# BMP085_Breakout-v14.net
KiCad netlist of a schematic drawn in EAGLE
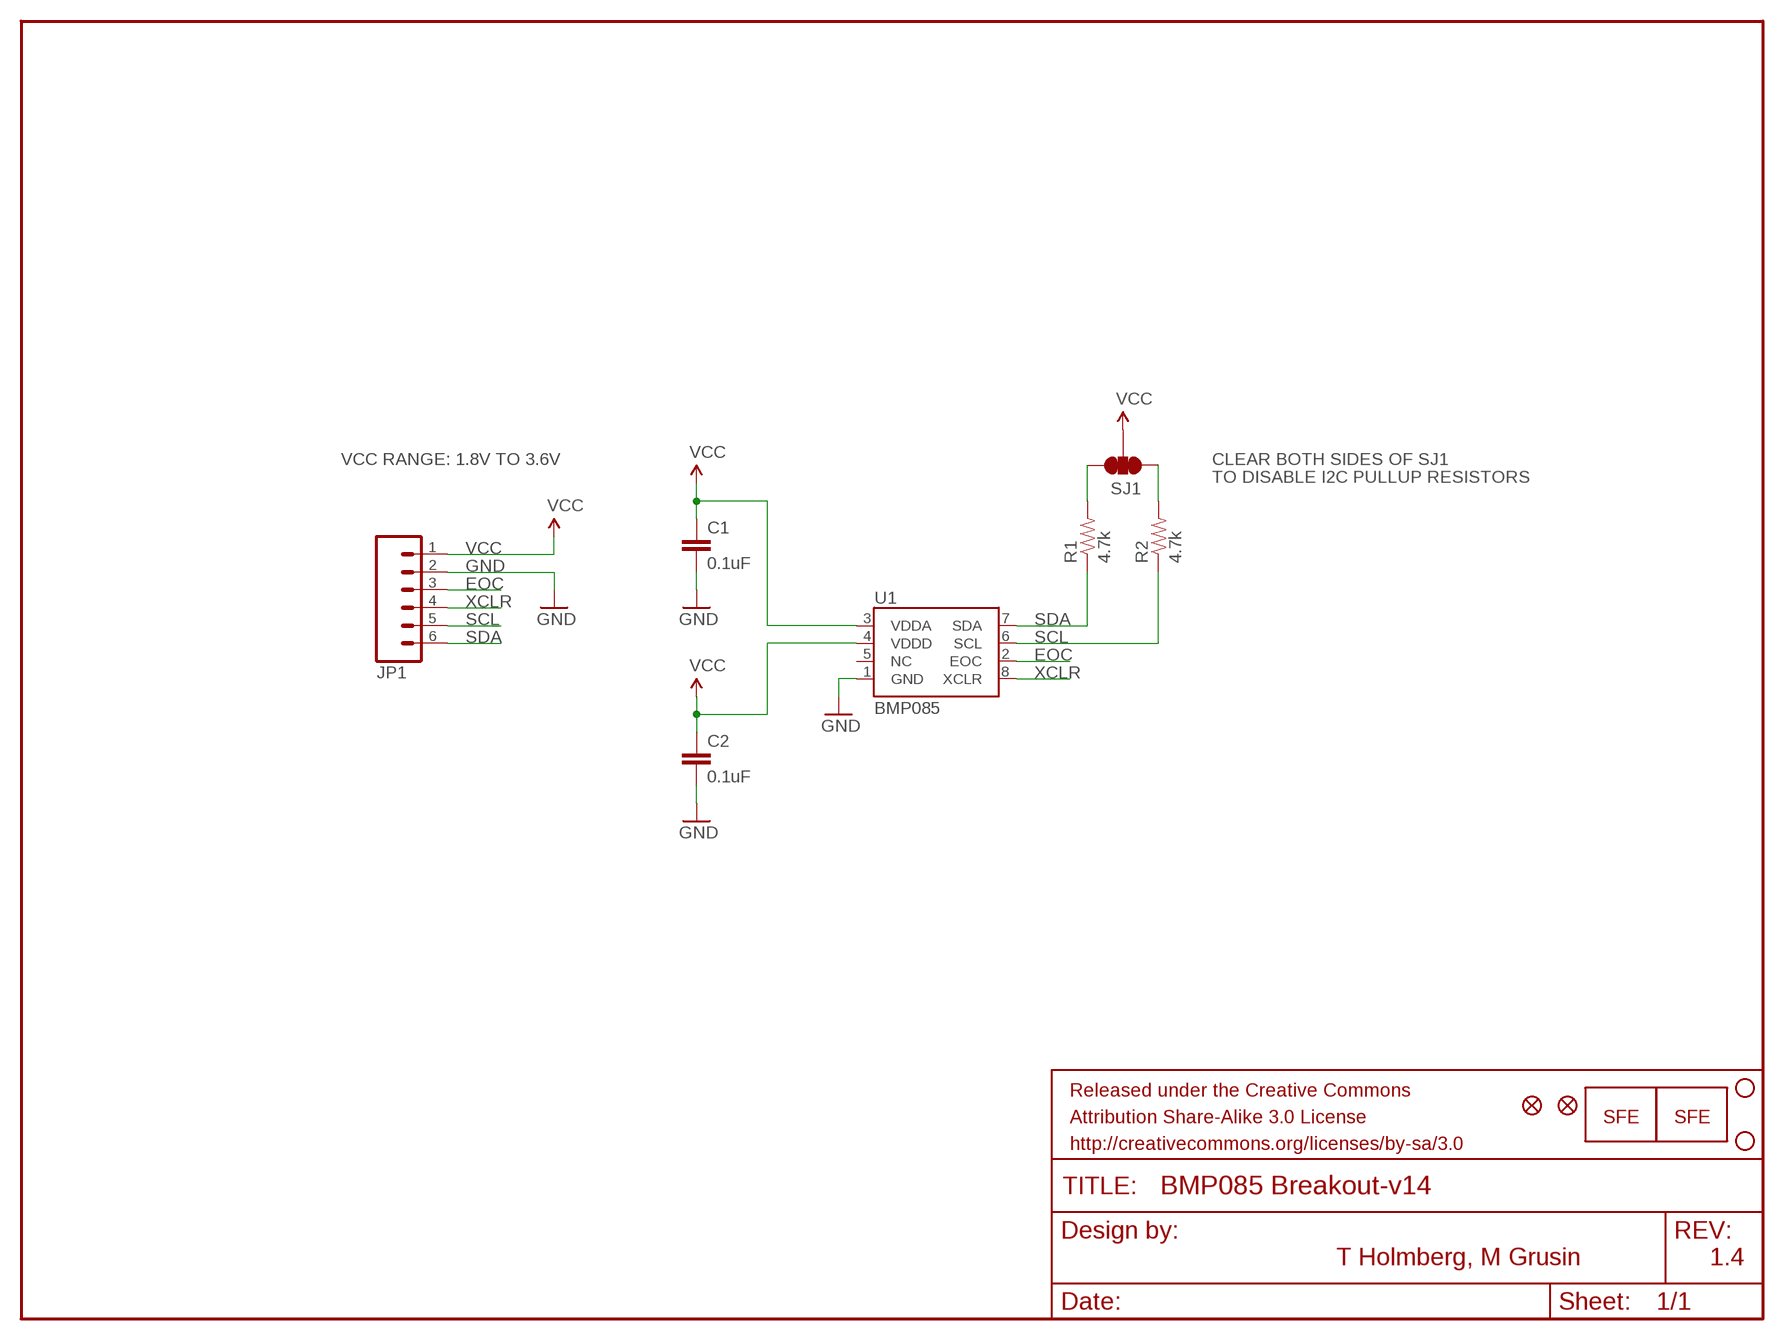
[diagram p0: schematic, sheet 1]

(export (version "E")
  (design (tool "Eeschema 10.0.6"))
  (components
    (comp (ref "C1")
      (value "0.1uF")
      (footprint "eagle-import:0402-CAP")
      (libsource (lib "eagle-import") (part "CAP0402-CAP"))
    )
    (comp (ref "C2")
      (value "0.1uF")
      (footprint "eagle-import:0402-CAP")
      (libsource (lib "eagle-import") (part "CAP0402-CAP"))
    )
    (comp (ref "JP1")
      (value "M06SIP")
      (footprint "eagle-import:1X06")
      (libsource (lib "eagle-import") (part "M06SIP"))
    )
    (comp (ref "JP2")
      (value "LOGO-SFENW2")
      (footprint "eagle-import:SFE-NEW-WEB")
      (libsource (lib "eagle-import") (part "SparkFun-Aesthetics_LOGO-SFENW2"))
    )
    (comp (ref "JP3")
      (value "FIDUCIALUFIDUCIAL")
      (footprint "eagle-import:MICRO-FIDUCIAL")
      (libsource (lib "eagle-import") (part "FIDUCIALUFIDUCIAL"))
    )
    (comp (ref "JP4")
      (value "FIDUCIALUFIDUCIAL")
      (footprint "eagle-import:MICRO-FIDUCIAL")
      (libsource (lib "eagle-import") (part "FIDUCIALUFIDUCIAL"))
    )
    (comp (ref "LOGO1")
      (value "LOGO-SFESK")
      (footprint "eagle-import:SFE-LOGO-FLAME")
      (libsource (lib "eagle-import") (part "LOGO-SFESK"))
    )
    (comp (ref "R1")
      (value "4.7k")
      (footprint "eagle-import:0402-RES")
      (libsource (lib "eagle-import") (part "RESISTOR0402-RES"))
    )
    (comp (ref "R2")
      (value "4.7k")
      (footprint "eagle-import:0402-RES")
      (libsource (lib "eagle-import") (part "RESISTOR0402-RES"))
    )
    (comp (ref "SJ1")
      (value "SOLDERJUMPER_2WAYPASTE1&2&3")
      (footprint "eagle-import:SJ_3_PASTE1&2&3")
      (libsource (lib "eagle-import") (part "SOLDERJUMPER_2WAYPASTE1&2&3"))
    )
    (comp (ref "STANDOFF1")
      (value "STAND-OFF")
      (footprint "eagle-import:STAND-OFF")
      (libsource (lib "eagle-import") (part "STAND-OFF"))
    )
    (comp (ref "STANDOFF2")
      (value "STAND-OFF")
      (footprint "eagle-import:STAND-OFF")
      (libsource (lib "eagle-import") (part "STAND-OFF"))
    )
    (comp (ref "U1")
      (value "BMP085")
      (footprint "eagle-import:BMP085")
      (libsource (lib "eagle-import") (part "BMP085"))
    )
  )
  (nets
    (net (code "1") (name "/EOC") (class "Default")
      (node (ref "JP1") (pin "3") (pinfunction "3_3") (pintype "passive"))
      (node (ref "U1") (pin "2") (pinfunction "EOC_2") (pintype "output"))
    )
    (net (code "2") (name "/SCL") (class "Default")
      (node (ref "JP1") (pin "5") (pinfunction "5_5") (pintype "passive"))
      (node (ref "R2") (pin "1") (pinfunction "1_1") (pintype "passive"))
      (node (ref "U1") (pin "6") (pinfunction "SCL_6") (pintype "input"))
    )
    (net (code "3") (name "/SDA") (class "Default")
      (node (ref "JP1") (pin "6") (pinfunction "6_6") (pintype "passive"))
      (node (ref "R1") (pin "1") (pinfunction "1_1") (pintype "passive"))
      (node (ref "U1") (pin "7") (pinfunction "SDA_7") (pintype "bidirectional"))
    )
    (net (code "4") (name "/XCLR") (class "Default")
      (node (ref "JP1") (pin "4") (pinfunction "4_4") (pintype "passive"))
      (node (ref "U1") (pin "8") (pinfunction "XCLR_8") (pintype "input"))
    )
    (net (code "5") (name "GND") (class "Default")
      (node (ref "C1") (pin "2") (pinfunction "2_2") (pintype "passive"))
      (node (ref "C2") (pin "2") (pinfunction "2_2") (pintype "passive"))
      (node (ref "JP1") (pin "2") (pinfunction "2_2") (pintype "passive"))
      (node (ref "U1") (pin "1") (pinfunction "GND_1") (pintype "power_in"))
    )
    (net (code "6") (name "Net-(R1-Pad2)") (class "Default")
      (node (ref "R1") (pin "2") (pinfunction "2_2") (pintype "passive"))
      (node (ref "SJ1") (pin "3") (pinfunction "3_3") (pintype "passive"))
    )
    (net (code "7") (name "Net-(R2-Pad2)") (class "Default")
      (node (ref "R2") (pin "2") (pinfunction "2_2") (pintype "passive"))
      (node (ref "SJ1") (pin "1") (pinfunction "1_1") (pintype "passive"))
    )
    (net (code "8") (name "VCC") (class "Default")
      (node (ref "C1") (pin "1") (pinfunction "1_1") (pintype "passive"))
      (node (ref "C2") (pin "1") (pinfunction "1_1") (pintype "passive"))
      (node (ref "JP1") (pin "1") (pinfunction "1_1") (pintype "passive"))
      (node (ref "SJ1") (pin "2") (pinfunction "2_2") (pintype "passive"))
      (node (ref "U1") (pin "3") (pinfunction "VDDA_3") (pintype "power_in"))
      (node (ref "U1") (pin "4") (pinfunction "VDDD_4") (pintype "power_in"))
    )
    (net (code "9") (name "unconnected-(U1-NC-Pad5)") (class "Default")
      (node (ref "U1") (pin "5") (pinfunction "NC_5") (pintype "bidirectional"))
    )
  )
)
